# hub.net
KiCad netlist of a schematic drawn in EAGLE
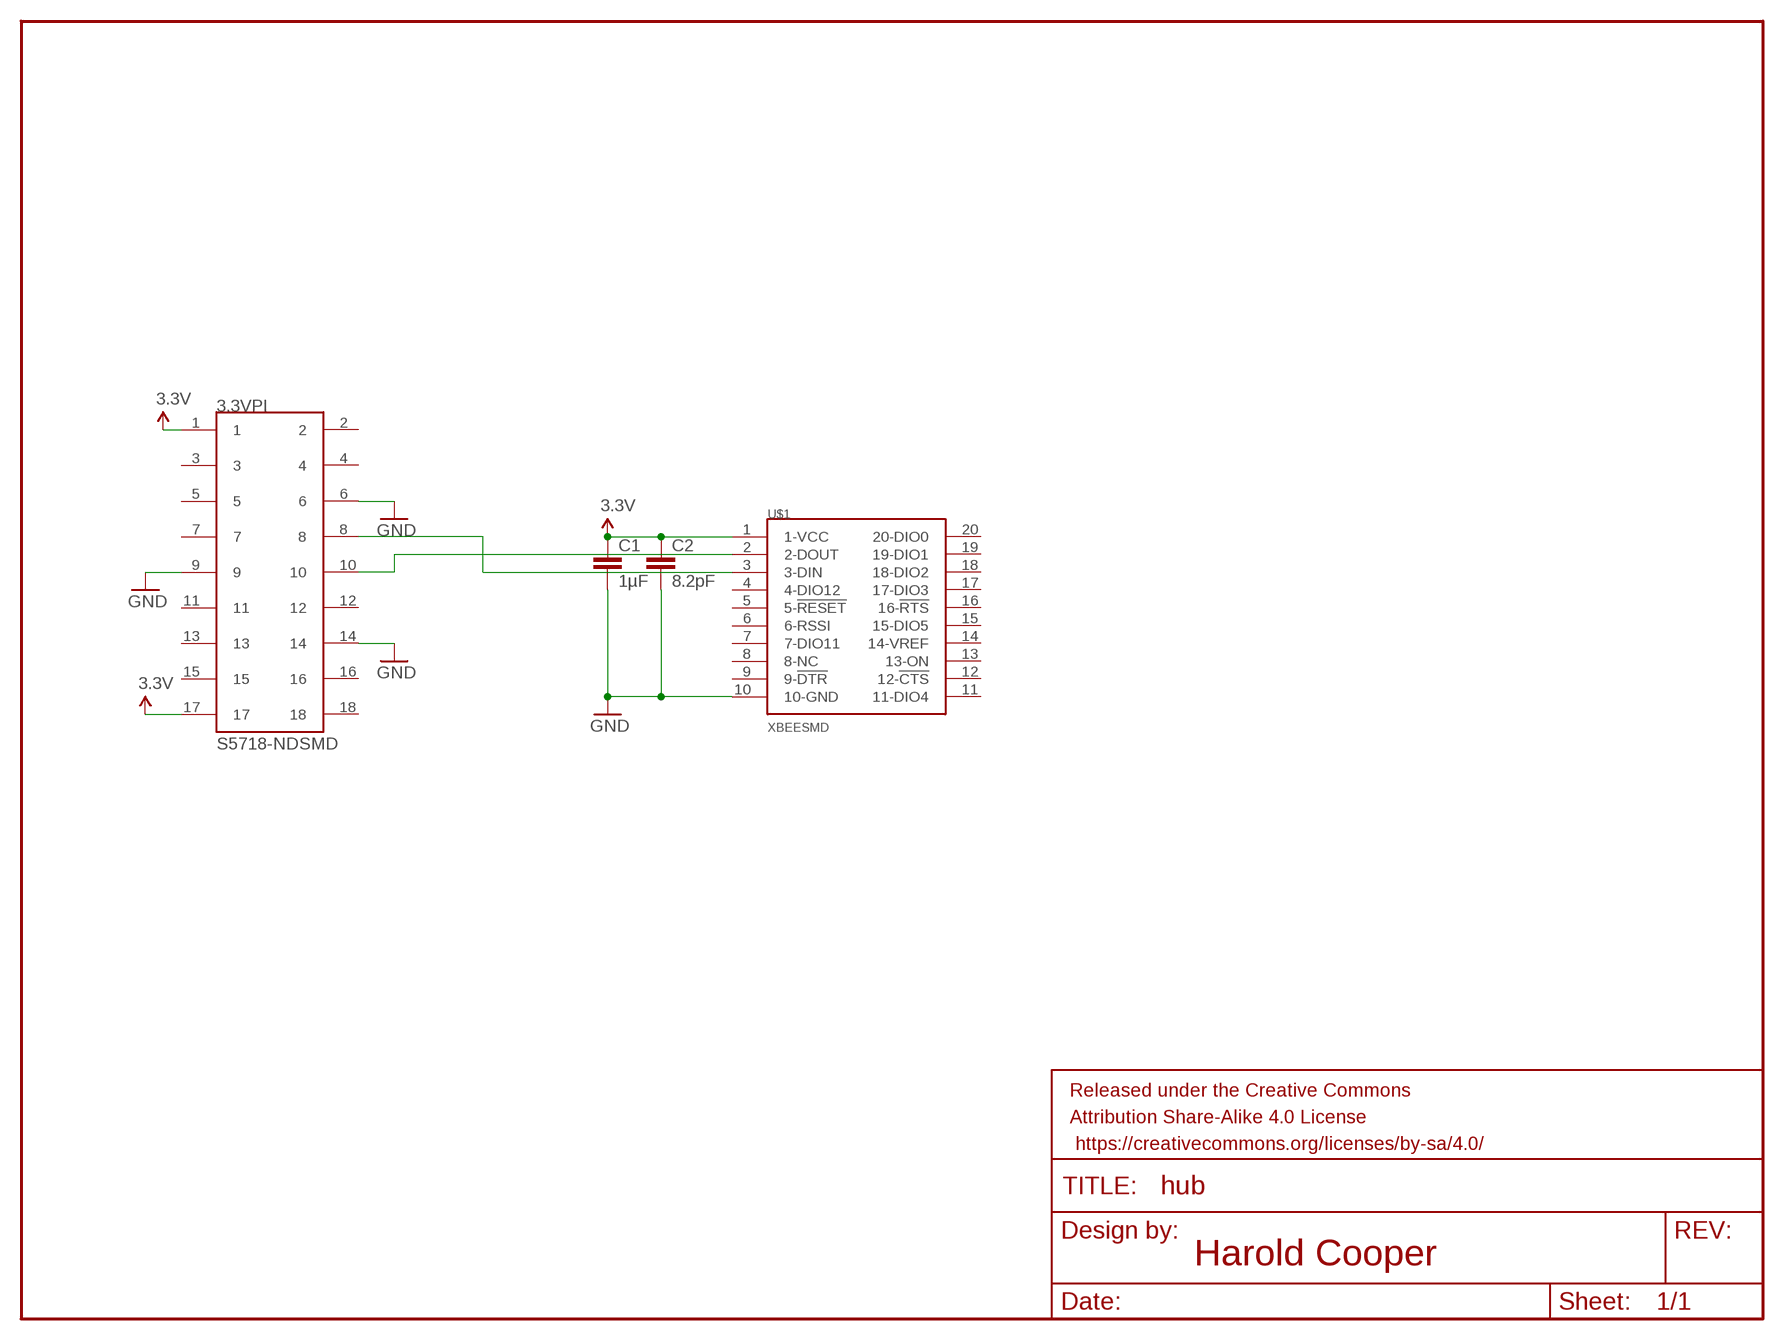
[diagram p0: schematic, sheet 1]

(export (version "E")
  (design (tool "Eeschema 10.0.6"))
  (components
    (comp (ref "3.3VPI")
      (value "S5718-NDSMD")
      (footprint "eagle-import:CONN_HEADER_SMD_18")
      (libsource (lib "eagle-import") (part "S5718-NDSMD"))
    )
    (comp (ref "C1")
      (value "1µF")
      (footprint "eagle-import:0805")
      (libsource (lib "eagle-import") (part "CAP0805"))
    )
    (comp (ref "C2")
      (value "8.2pF")
      (footprint "eagle-import:0805")
      (libsource (lib "eagle-import") (part "CAP0805"))
    )
    (comp (ref "FRAME1")
      (value "FRAME-LETTER")
      (footprint "eagle-import:CREATIVE_COMMONS")
      (libsource (lib "eagle-import") (part "FRAME-LETTER"))
    )
    (comp (ref "U$1")
      (value "XBEESMD")
      (footprint "eagle-import:CONN_HEADER_SMD_10X2")
      (libsource (lib "eagle-import") (part "XBEESMD"))
    )
  )
  (nets
    (net (code "1") (name "3.3V") (class "Default")
      (node (ref "3.3VPI") (pin "1") (pinfunction "1_1") (pintype "bidirectional"))
      (node (ref "3.3VPI") (pin "17") (pinfunction "17_17") (pintype "bidirectional"))
      (node (ref "C1") (pin "1") (pinfunction "1_1") (pintype "passive"))
      (node (ref "C2") (pin "1") (pinfunction "1_1") (pintype "passive"))
      (node (ref "U$1") (pin "1") (pinfunction "1-VCC_1") (pintype "bidirectional"))
    )
    (net (code "2") (name "GND") (class "Default")
      (node (ref "3.3VPI") (pin "14") (pinfunction "14_14") (pintype "bidirectional"))
      (node (ref "3.3VPI") (pin "6") (pinfunction "6_6") (pintype "bidirectional"))
      (node (ref "3.3VPI") (pin "9") (pinfunction "9_9") (pintype "bidirectional"))
      (node (ref "C1") (pin "2") (pinfunction "2_2") (pintype "passive"))
      (node (ref "C2") (pin "2") (pinfunction "2_2") (pintype "passive"))
      (node (ref "U$1") (pin "10") (pinfunction "10-GND_10") (pintype "bidirectional"))
    )
    (net (code "3") (name "Net-(U$1-2-DOUT)") (class "Default")
      (node (ref "3.3VPI") (pin "10") (pinfunction "10_10") (pintype "bidirectional"))
      (node (ref "U$1") (pin "2") (pinfunction "2-DOUT_2") (pintype "bidirectional"))
    )
    (net (code "4") (name "Net-(U$1-3-DIN)") (class "Default")
      (node (ref "3.3VPI") (pin "8") (pinfunction "8_8") (pintype "bidirectional"))
      (node (ref "U$1") (pin "3") (pinfunction "3-DIN_3") (pintype "bidirectional"))
    )
    (net (code "5") (name "unconnected-(3.3VPI-Pad2)") (class "Default")
      (node (ref "3.3VPI") (pin "2") (pinfunction "2_2") (pintype "bidirectional"))
    )
    (net (code "6") (name "unconnected-(3.3VPI-Pad3)") (class "Default")
      (node (ref "3.3VPI") (pin "3") (pinfunction "3_3") (pintype "bidirectional"))
    )
    (net (code "7") (name "unconnected-(3.3VPI-Pad4)") (class "Default")
      (node (ref "3.3VPI") (pin "4") (pinfunction "4_4") (pintype "bidirectional"))
    )
    (net (code "8") (name "unconnected-(3.3VPI-Pad5)") (class "Default")
      (node (ref "3.3VPI") (pin "5") (pinfunction "5_5") (pintype "bidirectional"))
    )
    (net (code "9") (name "unconnected-(3.3VPI-Pad7)") (class "Default")
      (node (ref "3.3VPI") (pin "7") (pinfunction "7_7") (pintype "bidirectional"))
    )
    (net (code "10") (name "unconnected-(3.3VPI-Pad11)") (class "Default")
      (node (ref "3.3VPI") (pin "11") (pinfunction "11_11") (pintype "bidirectional"))
    )
    (net (code "11") (name "unconnected-(3.3VPI-Pad12)") (class "Default")
      (node (ref "3.3VPI") (pin "12") (pinfunction "12_12") (pintype "bidirectional"))
    )
    (net (code "12") (name "unconnected-(3.3VPI-Pad13)") (class "Default")
      (node (ref "3.3VPI") (pin "13") (pinfunction "13_13") (pintype "bidirectional"))
    )
    (net (code "13") (name "unconnected-(3.3VPI-Pad15)") (class "Default")
      (node (ref "3.3VPI") (pin "15") (pinfunction "15_15") (pintype "bidirectional"))
    )
    (net (code "14") (name "unconnected-(3.3VPI-Pad16)") (class "Default")
      (node (ref "3.3VPI") (pin "16") (pinfunction "16_16") (pintype "bidirectional"))
    )
    (net (code "15") (name "unconnected-(3.3VPI-Pad18)") (class "Default")
      (node (ref "3.3VPI") (pin "18") (pinfunction "18_18") (pintype "bidirectional"))
    )
    (net (code "16") (name "unconnected-(U$1-4-DIO12-Pad4)") (class "Default")
      (node (ref "U$1") (pin "4") (pinfunction "4-DIO12_4") (pintype "bidirectional"))
    )
    (net (code "17") (name "unconnected-(U$1-5-~{RESET}-Pad5)") (class "Default")
      (node (ref "U$1") (pin "5") (pinfunction "5-~{RESET}_5") (pintype "bidirectional"))
    )
    (net (code "18") (name "unconnected-(U$1-6-RSSI-Pad6)") (class "Default")
      (node (ref "U$1") (pin "6") (pinfunction "6-RSSI_6") (pintype "bidirectional"))
    )
    (net (code "19") (name "unconnected-(U$1-7-DIO11-Pad7)") (class "Default")
      (node (ref "U$1") (pin "7") (pinfunction "7-DIO11_7") (pintype "bidirectional"))
    )
    (net (code "20") (name "unconnected-(U$1-8-NC-Pad8)") (class "Default")
      (node (ref "U$1") (pin "8") (pinfunction "8-NC_8") (pintype "bidirectional"))
    )
    (net (code "21") (name "unconnected-(U$1-9-~{DTR}-Pad9)") (class "Default")
      (node (ref "U$1") (pin "9") (pinfunction "9-~{DTR}_9") (pintype "bidirectional"))
    )
    (net (code "22") (name "unconnected-(U$1-11-DIO4-Pad11)") (class "Default")
      (node (ref "U$1") (pin "11") (pinfunction "11-DIO4_11") (pintype "bidirectional"))
    )
    (net (code "23") (name "unconnected-(U$1-12-~{CTS}-Pad12)") (class "Default")
      (node (ref "U$1") (pin "12") (pinfunction "12-~{CTS}_12") (pintype "bidirectional"))
    )
    (net (code "24") (name "unconnected-(U$1-13-ON-Pad13)") (class "Default")
      (node (ref "U$1") (pin "13") (pinfunction "13-ON_13") (pintype "bidirectional"))
    )
    (net (code "25") (name "unconnected-(U$1-14-VREF-Pad14)") (class "Default")
      (node (ref "U$1") (pin "14") (pinfunction "14-VREF_14") (pintype "bidirectional"))
    )
    (net (code "26") (name "unconnected-(U$1-15-DIO5-Pad15)") (class "Default")
      (node (ref "U$1") (pin "15") (pinfunction "15-DIO5_15") (pintype "bidirectional"))
    )
    (net (code "27") (name "unconnected-(U$1-16-~{RTS}-Pad16)") (class "Default")
      (node (ref "U$1") (pin "16") (pinfunction "16-~{RTS}_16") (pintype "bidirectional"))
    )
    (net (code "28") (name "unconnected-(U$1-17-DIO3-Pad17)") (class "Default")
      (node (ref "U$1") (pin "17") (pinfunction "17-DIO3_17") (pintype "bidirectional"))
    )
    (net (code "29") (name "unconnected-(U$1-18-DIO2-Pad18)") (class "Default")
      (node (ref "U$1") (pin "18") (pinfunction "18-DIO2_18") (pintype "bidirectional"))
    )
    (net (code "30") (name "unconnected-(U$1-19-DIO1-Pad19)") (class "Default")
      (node (ref "U$1") (pin "19") (pinfunction "19-DIO1_19") (pintype "bidirectional"))
    )
    (net (code "31") (name "unconnected-(U$1-20-DIO0-Pad20)") (class "Default")
      (node (ref "U$1") (pin "20") (pinfunction "20-DIO0_20") (pintype "bidirectional"))
    )
  )
)
